# T-Board-45-85_Etch_-_v0_1.net
KiCad netlist of a schematic drawn in EAGLE
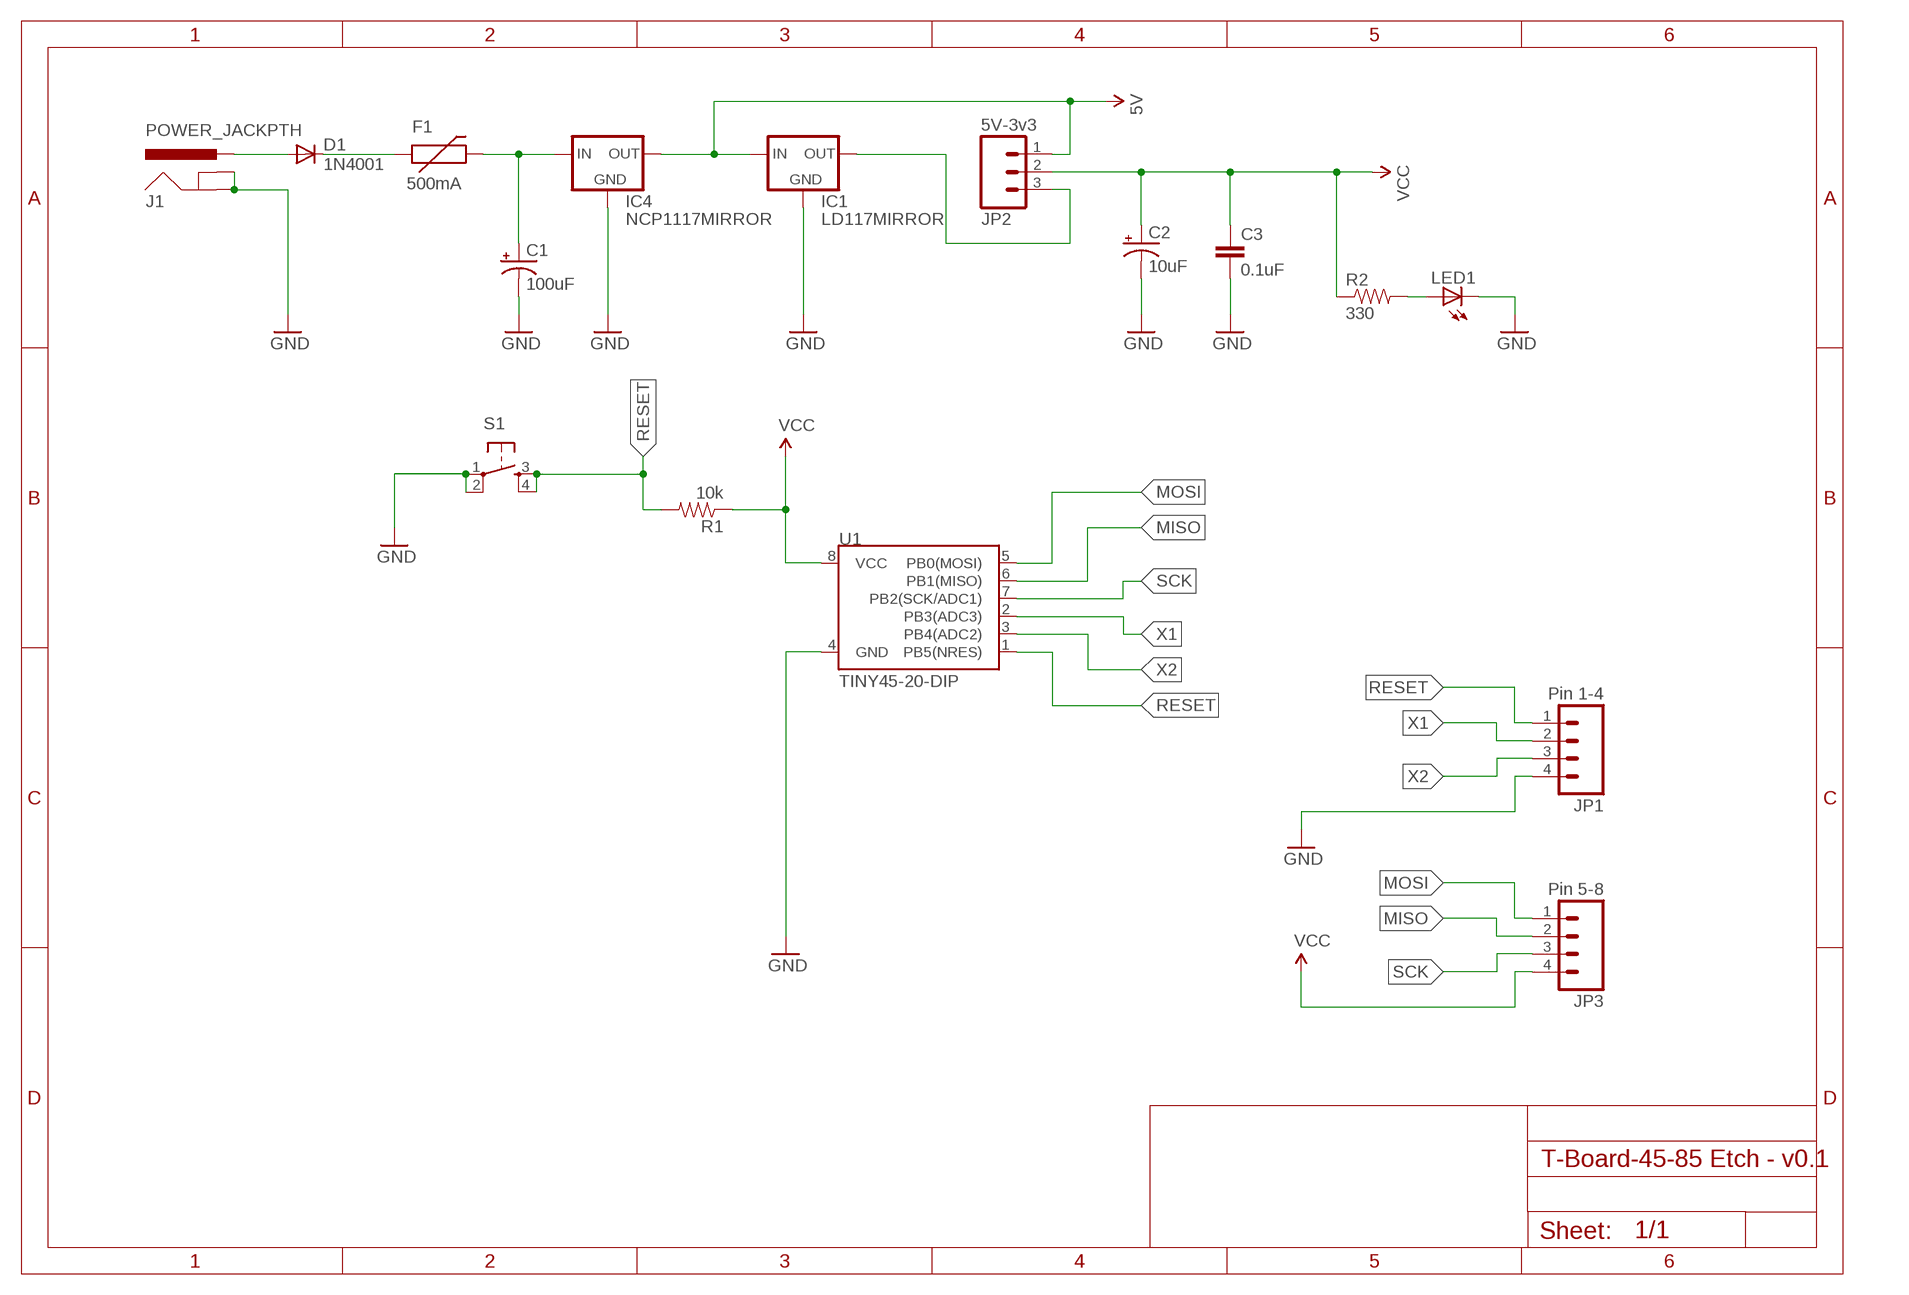
[diagram p0: schematic, sheet 1]

(export (version "E")
  (design (tool "Eeschema 10.0.6"))
  (components
    (comp (ref "C1")
      (value "100uF")
      (footprint "eagle-import:CPOL-RADIAL-100UF-25V")
      (libsource (lib "eagle-import") (part "CAP_POLPTH1"))
    )
    (comp (ref "C2")
      (value "10uF")
      (footprint "eagle-import:CPOL-RADIAL-10UF-25V")
      (libsource (lib "eagle-import") (part "CAP_POLPTH2"))
    )
    (comp (ref "C3")
      (value "0.1uF")
      (footprint "eagle-import:1206")
      (libsource (lib "eagle-import") (part "CAP1206"))
    )
    (comp (ref "D1")
      (value "1N4001")
      (footprint "eagle-import:DIODE-1N4001")
      (libsource (lib "eagle-import") (part "DIODEPTH"))
    )
    (comp (ref "F1")
      (value "500mA")
      (footprint "eagle-import:PTC")
      (libsource (lib "eagle-import") (part "PTCPTH"))
    )
    (comp (ref "IC1")
      (value "LD117MIRROR")
      (footprint "eagle-import:SOT223")
      (libsource (lib "eagle-import") (part "LD117MIRROR"))
    )
    (comp (ref "IC4")
      (value "NCP1117MIRROR")
      (footprint "eagle-import:DPACK")
      (libsource (lib "eagle-import") (part "NCP1117MIRROR"))
    )
    (comp (ref "J1")
      (value "POWER_JACKPTH")
      (footprint "eagle-import:POWER_JACK_PTH")
      (libsource (lib "eagle-import") (part "POWER_JACKPTH"))
    )
    (comp (ref "JP1")
      (value "Pin 1-4")
      (footprint "eagle-import:1X04")
      (libsource (lib "eagle-import") (part "M04-NON-POLARPTH"))
    )
    (comp (ref "JP2")
      (value "5V-3v3")
      (footprint "eagle-import:1X03")
      (libsource (lib "eagle-import") (part "M03PTH"))
    )
    (comp (ref "JP3")
      (value "Pin 5-8")
      (footprint "eagle-import:1X04")
      (libsource (lib "eagle-import") (part "M04-NON-POLARPTH"))
    )
    (comp (ref "LED1")
      (value "LED1206")
      (footprint "eagle-import:LED-1206")
      (libsource (lib "eagle-import") (part "LED1206"))
    )
    (comp (ref "R1")
      (value "10k")
      (footprint "eagle-import:1206")
      (libsource (lib "eagle-import") (part "RESISTOR1206"))
    )
    (comp (ref "R2")
      (value "330")
      (footprint "eagle-import:1206")
      (libsource (lib "eagle-import") (part "RESISTOR1206"))
    )
    (comp (ref "S1")
      (value "TAC_SWITCHPTH")
      (footprint "eagle-import:TACTILE-PTH")
      (libsource (lib "eagle-import") (part "TAC_SWITCHPTH"))
    )
    (comp (ref "U1")
      (value "TINY45-20-DIP")
      (footprint "eagle-import:DIP08")
      (libsource (lib "eagle-import") (part "ATTINY45TINY45-20-DIP"))
    )
  )
  (nets
    (net (code "1") (name "5V") (class "Default")
      (node (ref "IC1") (pin "1") (pinfunction "IN_1") (pintype "input"))
      (node (ref "IC4") (pin "4") (pinfunction "OUT_4") (pintype "passive"))
      (node (ref "JP2") (pin "1") (pinfunction "1_1") (pintype "passive"))
    )
    (net (code "2") (name "GND") (class "Default")
      (node (ref "C1") (pin "2") (pinfunction "-_2") (pintype "passive"))
      (node (ref "C2") (pin "2") (pinfunction "-_2") (pintype "passive"))
      (node (ref "C3") (pin "2") (pinfunction "2_2") (pintype "passive"))
      (node (ref "IC1") (pin "3") (pinfunction "GND_3") (pintype "input"))
      (node (ref "IC4") (pin "3") (pinfunction "GND_3") (pintype "input"))
      (node (ref "J1") (pin "GND") (pinfunction "GND_GND") (pintype "bidirectional"))
      (node (ref "J1") (pin "GNDBREAK") (pinfunction "GNDBREAK_GNDBREAK") (pintype "bidirectional"))
      (node (ref "JP1") (pin "4") (pinfunction "4_4") (pintype "passive"))
      (node (ref "LED1") (pin "C") (pinfunction "C_C") (pintype "passive"))
      (node (ref "S1") (pin "1") (pinfunction "1_1") (pintype "passive"))
      (node (ref "S1") (pin "2") (pinfunction "2_2") (pintype "passive"))
      (node (ref "U1") (pin "4") (pinfunction "GND_4") (pintype "bidirectional"))
    )
    (net (code "3") (name "MISO") (class "Default")
      (node (ref "JP3") (pin "2") (pinfunction "2_2") (pintype "passive"))
      (node (ref "U1") (pin "6") (pinfunction "PB1(MISO)_6") (pintype "bidirectional"))
    )
    (net (code "4") (name "MOSI") (class "Default")
      (node (ref "JP3") (pin "1") (pinfunction "1_1") (pintype "passive"))
      (node (ref "U1") (pin "5") (pinfunction "PB0(MOSI)_5") (pintype "bidirectional"))
    )
    (net (code "5") (name "Net-(C1-+)") (class "Default")
      (node (ref "C1") (pin "1") (pinfunction "+_1") (pintype "passive"))
      (node (ref "F1") (pin "P$2") (pinfunction "2_P$2") (pintype "bidirectional"))
      (node (ref "IC4") (pin "1") (pinfunction "IN_1") (pintype "input"))
    )
    (net (code "6") (name "Net-(D1-PadA)") (class "Default")
      (node (ref "D1") (pin "A") (pinfunction "A_A") (pintype "passive"))
      (node (ref "J1") (pin "PWR") (pinfunction "PWR_PWR") (pintype "bidirectional"))
    )
    (net (code "7") (name "Net-(F1-1)") (class "Default")
      (node (ref "D1") (pin "C") (pinfunction "C_C") (pintype "passive"))
      (node (ref "F1") (pin "P$1") (pinfunction "1_P$1") (pintype "bidirectional"))
    )
    (net (code "8") (name "Net-(IC1-OUT)") (class "Default")
      (node (ref "IC1") (pin "4") (pinfunction "OUT_4") (pintype "passive"))
      (node (ref "JP2") (pin "3") (pinfunction "3_3") (pintype "passive"))
    )
    (net (code "9") (name "Net-(LED1-PadA)") (class "Default")
      (node (ref "LED1") (pin "A") (pinfunction "A_A") (pintype "passive"))
      (node (ref "R2") (pin "2") (pinfunction "2_2") (pintype "passive"))
    )
    (net (code "10") (name "RESET") (class "Default")
      (node (ref "JP1") (pin "1") (pinfunction "1_1") (pintype "passive"))
      (node (ref "R1") (pin "2") (pinfunction "2_2") (pintype "passive"))
      (node (ref "S1") (pin "3") (pinfunction "3_3") (pintype "passive"))
      (node (ref "S1") (pin "4") (pinfunction "4_4") (pintype "passive"))
      (node (ref "U1") (pin "1") (pinfunction "PB5(NRES)_1") (pintype "bidirectional"))
    )
    (net (code "11") (name "SCK") (class "Default")
      (node (ref "JP3") (pin "3") (pinfunction "3_3") (pintype "passive"))
      (node (ref "U1") (pin "7") (pinfunction "PB2(SCK/ADC1)_7") (pintype "bidirectional"))
    )
    (net (code "12") (name "VCC") (class "Default")
      (node (ref "C2") (pin "1") (pinfunction "+_1") (pintype "passive"))
      (node (ref "C3") (pin "1") (pinfunction "1_1") (pintype "passive"))
      (node (ref "JP2") (pin "2") (pinfunction "2_2") (pintype "passive"))
      (node (ref "JP3") (pin "4") (pinfunction "4_4") (pintype "passive"))
      (node (ref "R1") (pin "1") (pinfunction "1_1") (pintype "passive"))
      (node (ref "R2") (pin "1") (pinfunction "1_1") (pintype "passive"))
      (node (ref "U1") (pin "8") (pinfunction "VCC_8") (pintype "bidirectional"))
    )
    (net (code "13") (name "X1") (class "Default")
      (node (ref "JP1") (pin "2") (pinfunction "2_2") (pintype "passive"))
      (node (ref "U1") (pin "2") (pinfunction "PB3(ADC3)_2") (pintype "bidirectional"))
    )
    (net (code "14") (name "X2") (class "Default")
      (node (ref "JP1") (pin "3") (pinfunction "3_3") (pintype "passive"))
      (node (ref "U1") (pin "3") (pinfunction "PB4(ADC2)_3") (pintype "bidirectional"))
    )
  )
)
